# Dashboard_Test_rev2.net
KiCad netlist of a schematic drawn in EAGLE
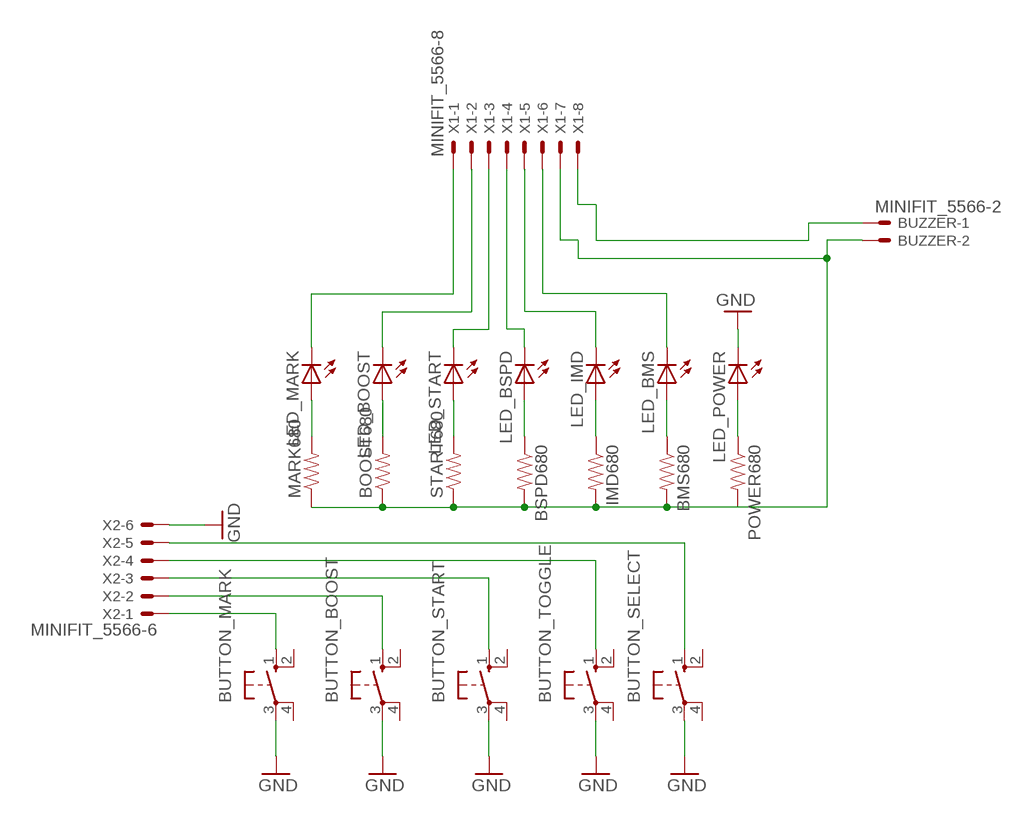
[diagram p0: schematic, sheet 1]

(export (version "E")
  (design (tool "Eeschema 10.0.6"))
  (components
    (comp (ref "BMS680")
      (value "RESISTOREZ")
      (footprint "eagle-import:AXIAL-0.3EZ")
      (libsource (lib "eagle-import") (part "RESISTOREZ"))
    )
    (comp (ref "BOOST680")
      (value "RESISTOREZ")
      (footprint "eagle-import:AXIAL-0.3EZ")
      (libsource (lib "eagle-import") (part "RESISTOREZ"))
    )
    (comp (ref "BSPD680")
      (value "RESISTOREZ")
      (footprint "eagle-import:AXIAL-0.3EZ")
      (libsource (lib "eagle-import") (part "RESISTOREZ"))
    )
    (comp (ref "BUTTON_BOOST")
      (value "BTN_10-XX")
      (footprint "eagle-import:B3F-10XX")
      (fields (field (name "MPN") "B3F-1000"))
      (libsource (lib "eagle-import") (part "BTN_10-XX"))
    )
    (comp (ref "BUTTON_MARK")
      (value "BTN_10-XX")
      (footprint "eagle-import:B3F-10XX")
      (fields (field (name "MPN") "B3F-1000"))
      (libsource (lib "eagle-import") (part "BTN_10-XX"))
    )
    (comp (ref "BUTTON_SELECT")
      (value "BTN_10-XX")
      (footprint "eagle-import:B3F-10XX")
      (fields (field (name "MPN") "B3F-1000"))
      (libsource (lib "eagle-import") (part "BTN_10-XX"))
    )
    (comp (ref "BUTTON_START")
      (value "BTN_10-XX")
      (footprint "eagle-import:B3F-10XX")
      (fields (field (name "MPN") "B3F-1000"))
      (libsource (lib "eagle-import") (part "BTN_10-XX"))
    )
    (comp (ref "BUTTON_TOGGLE")
      (value "BTN_10-XX")
      (footprint "eagle-import:B3F-10XX")
      (fields (field (name "MPN") "B3F-1000"))
      (libsource (lib "eagle-import") (part "BTN_10-XX"))
    )
    (comp (ref "BUZZER")
      (value "MINIFIT_5566-2")
      (footprint "eagle-import:MINIFIT_5566-2")
      (libsource (lib "eagle-import") (part "MINIFIT_5566-2"))
    )
    (comp (ref "IMD680")
      (value "RESISTOREZ")
      (footprint "eagle-import:AXIAL-0.3EZ")
      (libsource (lib "eagle-import") (part "RESISTOREZ"))
    )
    (comp (ref "LED_BMS")
      (value "LED-5MM")
      (footprint "eagle-import:LED-5MM")
      (libsource (lib "eagle-import") (part "LED-5MM"))
    )
    (comp (ref "LED_BOOST")
      (value "LED-5MM")
      (footprint "eagle-import:LED-5MM")
      (libsource (lib "eagle-import") (part "LED-5MM"))
    )
    (comp (ref "LED_BSPD")
      (value "LED-5MM")
      (footprint "eagle-import:LED-5MM")
      (libsource (lib "eagle-import") (part "LED-5MM"))
    )
    (comp (ref "LED_IMD")
      (value "LED-5MM")
      (footprint "eagle-import:LED-5MM")
      (libsource (lib "eagle-import") (part "LED-5MM"))
    )
    (comp (ref "LED_MARK")
      (value "LED-5MM")
      (footprint "eagle-import:LED-5MM")
      (libsource (lib "eagle-import") (part "LED-5MM"))
    )
    (comp (ref "LED_POWER")
      (value "LED-5MM")
      (footprint "eagle-import:LED-5MM")
      (libsource (lib "eagle-import") (part "LED-5MM"))
    )
    (comp (ref "LED_START")
      (value "LED-5MM")
      (footprint "eagle-import:LED-5MM")
      (libsource (lib "eagle-import") (part "LED-5MM"))
    )
    (comp (ref "MARK680")
      (value "RESISTOREZ")
      (footprint "eagle-import:AXIAL-0.3EZ")
      (libsource (lib "eagle-import") (part "RESISTOREZ"))
    )
    (comp (ref "POWER680")
      (value "RESISTOREZ")
      (footprint "eagle-import:AXIAL-0.3EZ")
      (libsource (lib "eagle-import") (part "RESISTOREZ"))
    )
    (comp (ref "START680")
      (value "RESISTOREZ")
      (footprint "eagle-import:AXIAL-0.3EZ")
      (libsource (lib "eagle-import") (part "RESISTOREZ"))
    )
    (comp (ref "X1")
      (value "MINIFIT_5566-8")
      (footprint "eagle-import:MINIFIT_5566-8")
      (libsource (lib "eagle-import") (part "MINIFIT_5566-8"))
    )
    (comp (ref "X2")
      (value "MINIFIT_5566-6")
      (footprint "eagle-import:MINIFIT_5566-6")
      (fields (field (name "MPN") "95566-61002"))
      (libsource (lib "eagle-import") (part "MINIFIT_5566-6"))
    )
  )
  (nets
    (net (code "1") (name "GND") (class "Default")
      (node (ref "BUTTON_BOOST") (pin "3") (pinfunction "P_3") (pintype "passive"))
      (node (ref "BUTTON_MARK") (pin "3") (pinfunction "P_3") (pintype "passive"))
      (node (ref "BUTTON_SELECT") (pin "3") (pinfunction "P_3") (pintype "passive"))
      (node (ref "BUTTON_START") (pin "3") (pinfunction "P_3") (pintype "passive"))
      (node (ref "BUTTON_TOGGLE") (pin "3") (pinfunction "P_3") (pintype "passive"))
      (node (ref "LED_POWER") (pin "K") (pinfunction "C_K") (pintype "passive"))
      (node (ref "X2") (pin "6") (pinfunction "S_6") (pintype "passive"))
    )
    (net (code "2") (name "Net-(BMS680-1)") (class "Default")
      (node (ref "BMS680") (pin "P$1") (pinfunction "1_P$1") (pintype "passive"))
      (node (ref "LED_BMS") (pin "A") (pinfunction "A_A") (pintype "passive"))
    )
    (net (code "3") (name "Net-(BMS680-2)") (class "Default")
      (node (ref "BMS680") (pin "P$2") (pinfunction "2_P$2") (pintype "passive"))
      (node (ref "BOOST680") (pin "P$1") (pinfunction "1_P$1") (pintype "passive"))
      (node (ref "BSPD680") (pin "P$2") (pinfunction "2_P$2") (pintype "passive"))
      (node (ref "BUZZER") (pin "2") (pinfunction "S_2") (pintype "passive"))
      (node (ref "IMD680") (pin "P$2") (pinfunction "2_P$2") (pintype "passive"))
      (node (ref "MARK680") (pin "P$1") (pinfunction "1_P$1") (pintype "passive"))
      (node (ref "POWER680") (pin "P$2") (pinfunction "2_P$2") (pintype "passive"))
      (node (ref "START680") (pin "P$1") (pinfunction "1_P$1") (pintype "passive"))
      (node (ref "X1") (pin "7") (pinfunction "S_7") (pintype "passive"))
    )
    (net (code "4") (name "Net-(BOOST680-2)") (class "Default")
      (node (ref "BOOST680") (pin "P$2") (pinfunction "2_P$2") (pintype "passive"))
      (node (ref "LED_BOOST") (pin "A") (pinfunction "A_A") (pintype "passive"))
    )
    (net (code "5") (name "Net-(BSPD680-1)") (class "Default")
      (node (ref "BSPD680") (pin "P$1") (pinfunction "1_P$1") (pintype "passive"))
      (node (ref "LED_BSPD") (pin "A") (pinfunction "A_A") (pintype "passive"))
    )
    (net (code "6") (name "Net-(BUTTON_BOOST-S)") (class "Default")
      (node (ref "BUTTON_BOOST") (pin "1") (pinfunction "S_1") (pintype "passive"))
      (node (ref "X2") (pin "2") (pinfunction "S_2") (pintype "passive"))
    )
    (net (code "7") (name "Net-(BUTTON_MARK-S)") (class "Default")
      (node (ref "BUTTON_MARK") (pin "1") (pinfunction "S_1") (pintype "passive"))
      (node (ref "X2") (pin "1") (pinfunction "S_1") (pintype "passive"))
    )
    (net (code "8") (name "Net-(BUTTON_SELECT-S)") (class "Default")
      (node (ref "BUTTON_SELECT") (pin "1") (pinfunction "S_1") (pintype "passive"))
      (node (ref "X2") (pin "5") (pinfunction "S_5") (pintype "passive"))
    )
    (net (code "9") (name "Net-(BUTTON_START-S)") (class "Default")
      (node (ref "BUTTON_START") (pin "1") (pinfunction "S_1") (pintype "passive"))
      (node (ref "X2") (pin "3") (pinfunction "S_3") (pintype "passive"))
    )
    (net (code "10") (name "Net-(BUTTON_TOGGLE-S)") (class "Default")
      (node (ref "BUTTON_TOGGLE") (pin "1") (pinfunction "S_1") (pintype "passive"))
      (node (ref "X2") (pin "4") (pinfunction "S_4") (pintype "passive"))
    )
    (net (code "11") (name "Net-(BUZZERA-S)") (class "Default")
      (node (ref "BUZZER") (pin "1") (pinfunction "S_1") (pintype "passive"))
      (node (ref "X1") (pin "8") (pinfunction "S_8") (pintype "passive"))
    )
    (net (code "12") (name "Net-(IMD680-1)") (class "Default")
      (node (ref "IMD680") (pin "P$1") (pinfunction "1_P$1") (pintype "passive"))
      (node (ref "LED_IMD") (pin "A") (pinfunction "A_A") (pintype "passive"))
    )
    (net (code "13") (name "Net-(LED_BMS-C)") (class "Default")
      (node (ref "LED_BMS") (pin "K") (pinfunction "C_K") (pintype "passive"))
      (node (ref "X1") (pin "6") (pinfunction "S_6") (pintype "passive"))
    )
    (net (code "14") (name "Net-(LED_BOOST-C)") (class "Default")
      (node (ref "LED_BOOST") (pin "K") (pinfunction "C_K") (pintype "passive"))
      (node (ref "X1") (pin "2") (pinfunction "S_2") (pintype "passive"))
    )
    (net (code "15") (name "Net-(LED_BSPD-C)") (class "Default")
      (node (ref "LED_BSPD") (pin "K") (pinfunction "C_K") (pintype "passive"))
      (node (ref "X1") (pin "4") (pinfunction "S_4") (pintype "passive"))
    )
    (net (code "16") (name "Net-(LED_IMD-C)") (class "Default")
      (node (ref "LED_IMD") (pin "K") (pinfunction "C_K") (pintype "passive"))
      (node (ref "X1") (pin "5") (pinfunction "S_5") (pintype "passive"))
    )
    (net (code "17") (name "Net-(LED_MARK-C)") (class "Default")
      (node (ref "LED_MARK") (pin "K") (pinfunction "C_K") (pintype "passive"))
      (node (ref "X1") (pin "1") (pinfunction "S_1") (pintype "passive"))
    )
    (net (code "18") (name "Net-(LED_START-C)") (class "Default")
      (node (ref "LED_START") (pin "K") (pinfunction "C_K") (pintype "passive"))
      (node (ref "X1") (pin "3") (pinfunction "S_3") (pintype "passive"))
    )
    (net (code "19") (name "Net-(MARK680-2)") (class "Default")
      (node (ref "LED_MARK") (pin "A") (pinfunction "A_A") (pintype "passive"))
      (node (ref "MARK680") (pin "P$2") (pinfunction "2_P$2") (pintype "passive"))
    )
    (net (code "20") (name "Net-(POWER680-1)") (class "Default")
      (node (ref "LED_POWER") (pin "A") (pinfunction "A_A") (pintype "passive"))
      (node (ref "POWER680") (pin "P$1") (pinfunction "1_P$1") (pintype "passive"))
    )
    (net (code "21") (name "Net-(START680-2)") (class "Default")
      (node (ref "LED_START") (pin "A") (pinfunction "A_A") (pintype "passive"))
      (node (ref "START680") (pin "P$2") (pinfunction "2_P$2") (pintype "passive"))
    )
    (net (code "22") (name "unconnected-(BUTTON_BOOST-P1-Pad4)") (class "Default")
      (node (ref "BUTTON_BOOST") (pin "4") (pinfunction "P1_4") (pintype "passive"))
    )
    (net (code "23") (name "unconnected-(BUTTON_BOOST-S1-Pad2)") (class "Default")
      (node (ref "BUTTON_BOOST") (pin "2") (pinfunction "S1_2") (pintype "passive"))
    )
    (net (code "24") (name "unconnected-(BUTTON_MARK-P1-Pad4)") (class "Default")
      (node (ref "BUTTON_MARK") (pin "4") (pinfunction "P1_4") (pintype "passive"))
    )
    (net (code "25") (name "unconnected-(BUTTON_MARK-S1-Pad2)") (class "Default")
      (node (ref "BUTTON_MARK") (pin "2") (pinfunction "S1_2") (pintype "passive"))
    )
    (net (code "26") (name "unconnected-(BUTTON_SELECT-P1-Pad4)") (class "Default")
      (node (ref "BUTTON_SELECT") (pin "4") (pinfunction "P1_4") (pintype "passive"))
    )
    (net (code "27") (name "unconnected-(BUTTON_SELECT-S1-Pad2)") (class "Default")
      (node (ref "BUTTON_SELECT") (pin "2") (pinfunction "S1_2") (pintype "passive"))
    )
    (net (code "28") (name "unconnected-(BUTTON_START-P1-Pad4)") (class "Default")
      (node (ref "BUTTON_START") (pin "4") (pinfunction "P1_4") (pintype "passive"))
    )
    (net (code "29") (name "unconnected-(BUTTON_START-S1-Pad2)") (class "Default")
      (node (ref "BUTTON_START") (pin "2") (pinfunction "S1_2") (pintype "passive"))
    )
    (net (code "30") (name "unconnected-(BUTTON_TOGGLE-P1-Pad4)") (class "Default")
      (node (ref "BUTTON_TOGGLE") (pin "4") (pinfunction "P1_4") (pintype "passive"))
    )
    (net (code "31") (name "unconnected-(BUTTON_TOGGLE-S1-Pad2)") (class "Default")
      (node (ref "BUTTON_TOGGLE") (pin "2") (pinfunction "S1_2") (pintype "passive"))
    )
  )
)
